# Sensors.net
KiCad netlist of a schematic drawn in Altium Designer
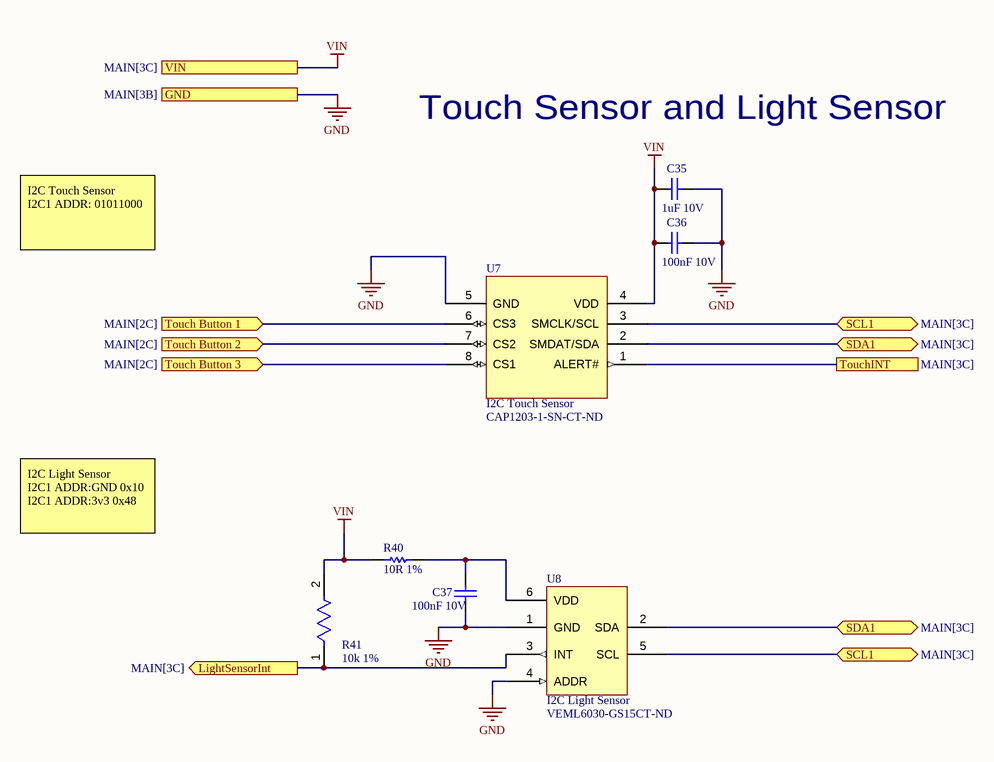
[diagram p0: Sensors.SchDoc]

(export (version "E")
  (design (tool "Eeschema 10.0.6"))
  (components
    (comp (ref "C35")
      (value "1uF 10V")
      (footprint "CAPC0402(1005)60_N")
      (description "CAP 1uF 10V ±10% 0402 (1005 Metric) Thickness 0.6mm SMD")
      (fields (field (name "TOLERANCE") "Â±10%"))
      (libsource (lib "Altium Content Vault") (part "CAP"))
    )
    (comp (ref "C36")
      (value "100nF 10V")
      (footprint "CAPC0402(1005)60_L")
      (description "CAP 100nF 10V ±5% 0402 (1005 Metric) Thickness 0.6mm SMD")
      (fields (field (name "TOLERANCE") "Â±5%"))
      (libsource (lib "Altium Content Vault") (part "CAP"))
    )
    (comp (ref "C37")
      (value "100nF 10V")
      (footprint "CAPC0402(1005)60_L")
      (description "CAP 100nF 10V ±5% 0402 (1005 Metric) Thickness 0.6mm SMD")
      (fields (field (name "TOLERANCE") "Â±5%"))
      (libsource (lib "Altium Content Vault") (part "CAP"))
    )
    (comp (ref "R40")
      (value "10R 1%")
      (footprint "RESC0402(1005)_N")
      (description "10R 0.063W 1% 0402 (1005 Metric)  SMD")
      (fields (field (name "POWER") "0.063 W") (field (name "TOLERANCE") "1 %"))
      (libsource (lib "Altium Content Vault") (part "RES"))
    )
    (comp (ref "R41")
      (value "10k 1%")
      (footprint "FP-CRCW0402-e3-IPC_C")
      (description "RES Thick Film, 10kΩ, 1%, 0.063W, 100ppm/°C, 0402")
      (fields (field (name "TOLERANCE") "1%"))
      (libsource (lib "Altium Content Vault") (part "1029c3af85768c4190bb7ad29bc67b5"))
    )
    (comp (ref "U7")
      (value "I2C Touch Sensor")
      (footprint "CAP1203-1-SN-TR")
      (description "Sensor Controller Capacitive 3-CH I2C 8-Pin SOIC T/R")
      (fields
        (field (name "MANUFACTURER") "Microchip")
        (field (name "MANUFACTURER PART NUMBER") "CAP1203-1-SN-TR")
        (field (name "SUPPLIER PART NUMBER 1") "CAP1203-1-SN-CT-ND")
      )
      (libsource (lib "ESE516A2") (part "CAP1203-1-SN-TR"))
    )
    (comp (ref "U8")
      (value "I2C Light Sensor")
      (footprint "CAC-65P200X200-6N")
      (description "HIGH ACCURACY AMBIENT LIGHT SENS")
      (fields
        (field (name "MANUFACTURER") "Vishay Semiconductors")
        (field (name "MANUFACTURER PART NUMBER") "VEML6030-GS15")
        (field (name "SUPPLIER PART NUMBER 1") "VEML6030-GS15CT-ND")
      )
      (libsource (lib "ESE516A2") (part "VEML6030-GS15"))
    )
  )
  (nets
    (net (code "1") (name "/LightSensorInt") (class "Default")
      (node (ref "R41") (pin "1") (pinfunction "1_1") (pintype "passive"))
      (node (ref "U8") (pin "3") (pinfunction "INT_3") (pintype "output"))
    )
    (net (code "2") (name "/SCL1") (class "Default")
      (node (ref "U7") (pin "3") (pinfunction "SMCLK/SCL_3") (pintype "open_collector"))
      (node (ref "U8") (pin "5") (pinfunction "SCL_5") (pintype "open_collector"))
    )
    (net (code "3") (name "/SDA1") (class "Default")
      (node (ref "U7") (pin "2") (pinfunction "SMDAT/SDA_2") (pintype "open_collector"))
      (node (ref "U8") (pin "2") (pinfunction "SDA_2") (pintype "open_collector"))
    )
    (net (code "4") (name "/Touch Button 1") (class "Default")
      (node (ref "U7") (pin "6") (pinfunction "CS3_6") (pintype "bidirectional"))
    )
    (net (code "5") (name "/Touch Button 2") (class "Default")
      (node (ref "U7") (pin "7") (pinfunction "CS2_7") (pintype "bidirectional"))
    )
    (net (code "6") (name "/Touch Button 3") (class "Default")
      (node (ref "U7") (pin "8") (pinfunction "CS1_8") (pintype "bidirectional"))
    )
    (net (code "7") (name "/TouchINT") (class "Default")
      (node (ref "U7") (pin "1") (pinfunction "ALERT#_1") (pintype "output"))
    )
    (net (code "8") (name "GND") (class "Default")
      (node (ref "C35") (pin "2") (pinfunction "2_2") (pintype "passive"))
      (node (ref "C36") (pin "2") (pinfunction "2_2") (pintype "passive"))
      (node (ref "C37") (pin "1") (pinfunction "1_1") (pintype "passive"))
      (node (ref "U7") (pin "5") (pinfunction "GND_5") (pintype "power_in"))
      (node (ref "U8") (pin "1") (pinfunction "GND_1") (pintype "power_in"))
      (node (ref "U8") (pin "4") (pinfunction "ADDR_4") (pintype "input"))
    )
    (net (code "9") (name "Net-(U8-VDD)") (class "Default")
      (node (ref "C37") (pin "2") (pinfunction "2_2") (pintype "passive"))
      (node (ref "R40") (pin "2") (pinfunction "2_2") (pintype "passive"))
      (node (ref "U8") (pin "6") (pinfunction "VDD_6") (pintype "power_in"))
    )
    (net (code "10") (name "VIN") (class "Default")
      (node (ref "C35") (pin "1") (pinfunction "1_1") (pintype "passive"))
      (node (ref "C36") (pin "1") (pinfunction "1_1") (pintype "passive"))
      (node (ref "R40") (pin "1") (pinfunction "1_1") (pintype "passive"))
      (node (ref "R41") (pin "2") (pinfunction "2_2") (pintype "passive"))
      (node (ref "U7") (pin "4") (pinfunction "VDD_4") (pintype "power_in"))
    )
  )
)
